# band-psd-micro-standalone.net
KiCad netlist of a schematic drawn in EAGLE
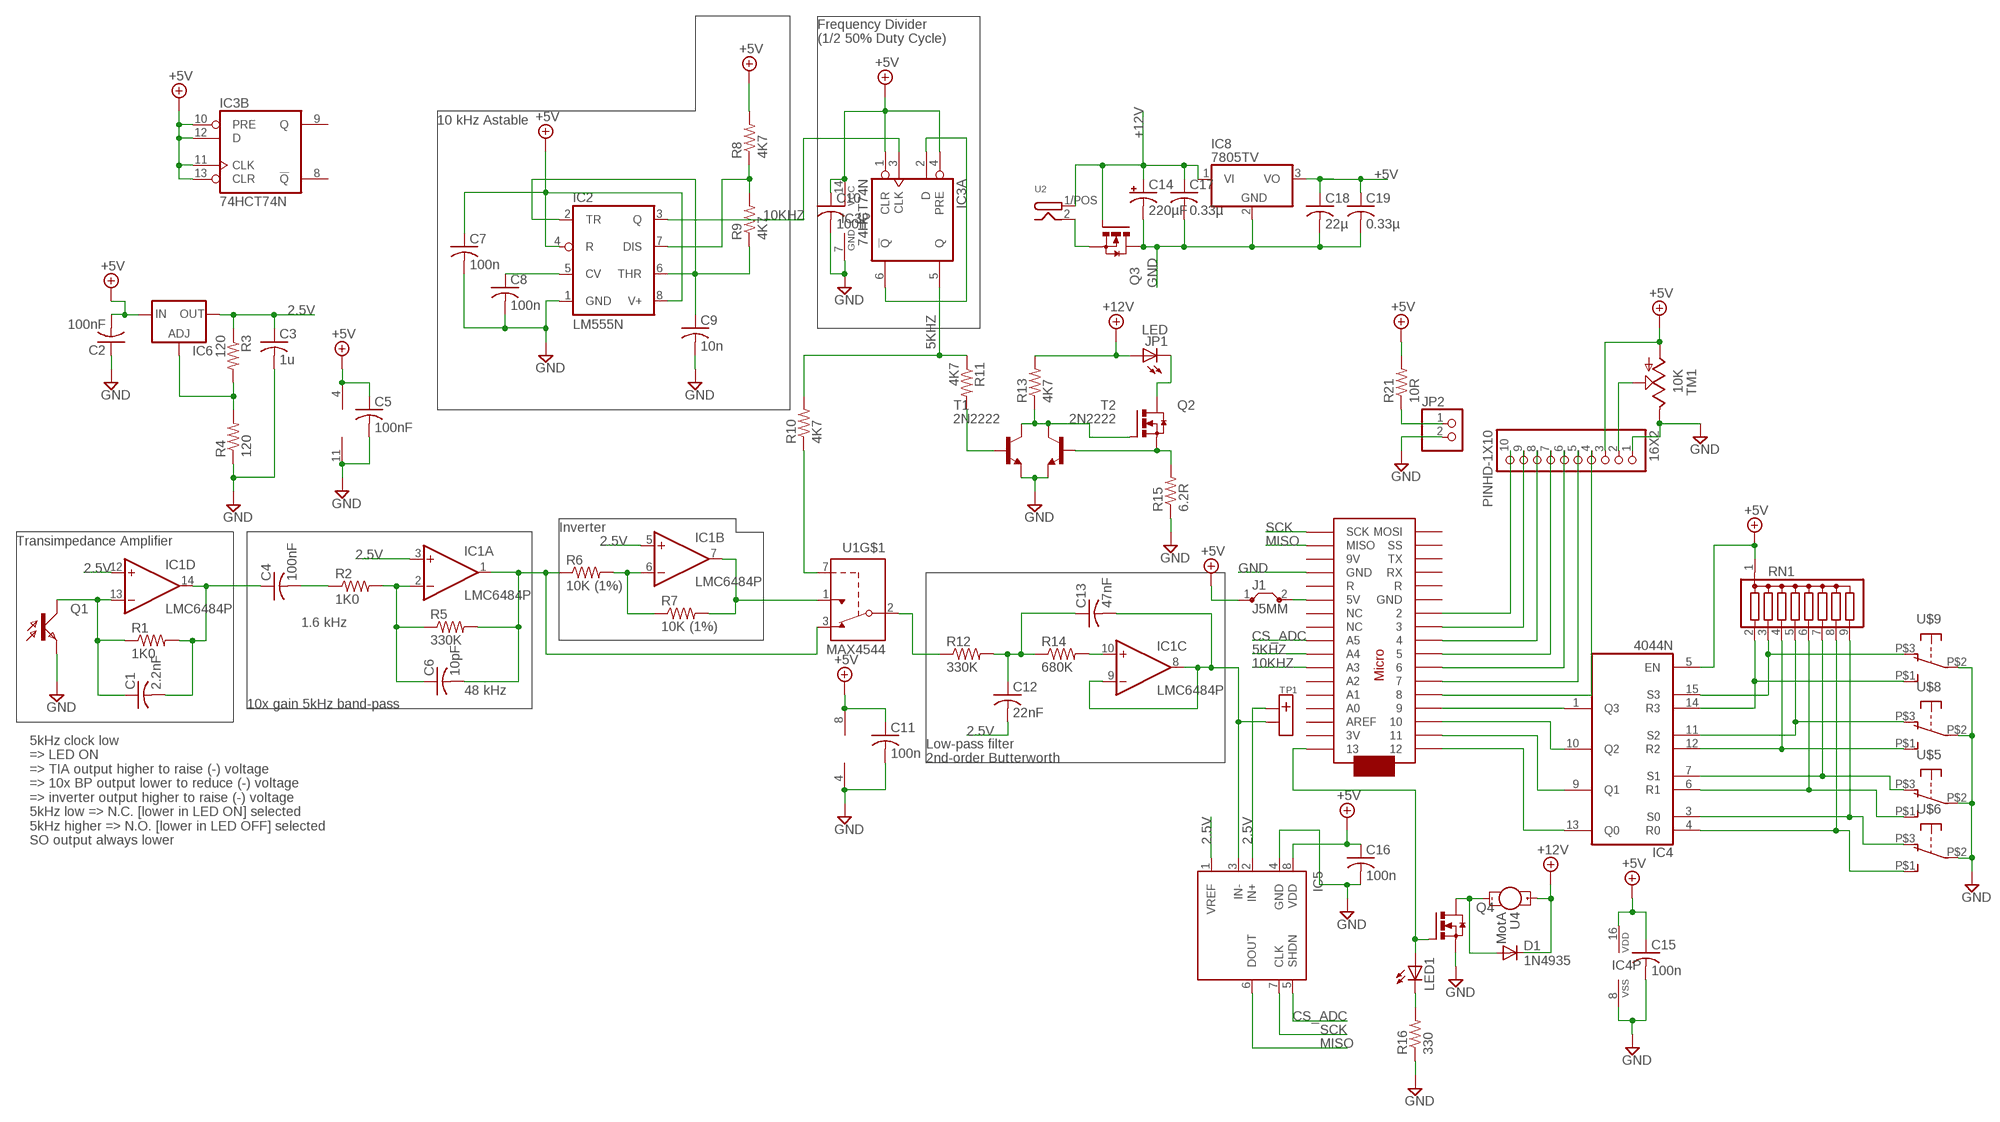
[diagram p0: schematic, sheet 1]

(export (version "E")
  (design (tool "Eeschema 10.0.6"))
  (components
    (comp (ref "16X2")
      (value "PINHD-1X10")
      (footprint "eagle-import:1X10-BIG")
      (libsource (lib "eagle-import") (part "PINHD-1X10"))
    )
    (comp (ref "C1")
      (value "2.2nF")
      (footprint "eagle-import:C025-024X044")
      (fields (field (name "MANF") "Vishay BC Components"))
      (libsource (lib "eagle-import") (part "C-US025-024X044"))
    )
    (comp (ref "C2")
      (value "100nF")
      (footprint "eagle-import:C025-025X050")
      (fields (field (name "MANF") "Vishay BC Components"))
      (libsource (lib "eagle-import") (part "C-US025-025X050"))
    )
    (comp (ref "C3")
      (value "1u")
      (footprint "eagle-import:C050-024X044")
      (fields (field (name "MANF") "TDK Corporation"))
      (libsource (lib "eagle-import") (part "C-US050-024X044"))
    )
    (comp (ref "C4")
      (value "100nF")
      (footprint "eagle-import:C025-060X050")
      (fields (field (name "MANF") "TDK Corporation"))
      (libsource (lib "eagle-import") (part "C-US025-060X050"))
    )
    (comp (ref "C5")
      (value "100nF")
      (footprint "eagle-import:C025-025X050")
      (libsource (lib "eagle-import") (part "C-US025-025X050"))
    )
    (comp (ref "C6")
      (value "10pF")
      (footprint "eagle-import:C025-024X044")
      (fields (field (name "MANF") "Vishay BC Components"))
      (libsource (lib "eagle-import") (part "C-US025-024X044"))
    )
    (comp (ref "C7")
      (value "100n")
      (footprint "eagle-import:C025-025X050")
      (libsource (lib "eagle-import") (part "C-US025-025X050"))
    )
    (comp (ref "C8")
      (value "100n")
      (footprint "eagle-import:C025-025X050")
      (libsource (lib "eagle-import") (part "C-US025-025X050"))
    )
    (comp (ref "C9")
      (value "10n")
      (footprint "eagle-import:C025-025X050")
      (fields (field (name "MANF") "TDK Corporation"))
      (libsource (lib "eagle-import") (part "C-US025-025X050"))
    )
    (comp (ref "C10")
      (value "100n")
      (footprint "eagle-import:C025-025X050")
      (libsource (lib "eagle-import") (part "C-US025-025X050"))
    )
    (comp (ref "C11")
      (value "100n")
      (footprint "eagle-import:C025-025X050")
      (libsource (lib "eagle-import") (part "C-US025-025X050"))
    )
    (comp (ref "C12")
      (value "22nF")
      (footprint "eagle-import:C025-024X044")
      (fields (field (name "MANF") "TDK Corporation"))
      (libsource (lib "eagle-import") (part "C-US025-024X044"))
    )
    (comp (ref "C13")
      (value "47nF")
      (footprint "eagle-import:C025-040X050")
      (fields (field (name "MANF") "TDK Corporation"))
      (libsource (lib "eagle-import") (part "C-US025-040X050"))
    )
    (comp (ref "C14")
      (value "220µF")
      (footprint "eagle-import:E3,5-8")
      (fields (field (name "MANF") "Panasonic Electronic Components"))
      (libsource (lib "eagle-import") (part "CPOL-USE3.5-8"))
    )
    (comp (ref "C15")
      (value "100n")
      (footprint "eagle-import:C025-025X050")
      (libsource (lib "eagle-import") (part "C-US025-025X050"))
    )
    (comp (ref "C16")
      (value "100n")
      (footprint "eagle-import:C025-025X050")
      (libsource (lib "eagle-import") (part "C-US025-025X050"))
    )
    (comp (ref "C17")
      (value "0.33µ")
      (footprint "eagle-import:C025-050X050")
      (fields (field (name "MANF") "TDK Corporation"))
      (libsource (lib "eagle-import") (part "C-US025-050X050"))
    )
    (comp (ref "C18")
      (value "22µ")
      (footprint "eagle-import:C050-045X075")
      (fields (field (name "MANF") "TDK Corporation"))
      (libsource (lib "eagle-import") (part "C-US050-045X075"))
    )
    (comp (ref "C19")
      (value "0.33µ")
      (footprint "eagle-import:C025-050X050")
      (fields (field (name "MANF") "TDK Corporation"))
      (libsource (lib "eagle-import") (part "C-US025-050X050"))
    )
    (comp (ref "D1")
      (value "1N4935")
      (footprint "eagle-import:DO41-10")
      (fields (field (name "MANF") "Fairchild Semiconductor"))
      (libsource (lib "eagle-import") (part "1N4004"))
    )
    (comp (ref "IC1")
      (value "LMC6484P")
      (footprint "eagle-import:DIL14")
      (fields
        (field (name "DIGIKEY#") "LMC6484AIN/NOPB-ND")
        (field (name "DIGIKEY2#") "AE10012-ND")
        (field (name "MANF") "Texas Instruments")
        (field (name "MANF#") "LMC6484AIN/NOPB")
      )
      (libsource (lib "eagle-import") (part "LMC6484P"))
    )
    (comp (ref "IC2")
      (value "LM555N")
      (footprint "eagle-import:DIL08")
      (fields (field (name "MANF") "Fairchild Semiconductor"))
      (libsource (lib "eagle-import") (part "555NLM"))
    )
    (comp (ref "IC3")
      (value "74HCT74N")
      (footprint "eagle-import:DIL14")
      (fields
        (field (name "DIGIKEY#") "296-1625-5-ND ")
        (field (name "DIGIKEY2#") "AE10012-ND")
        (field (name "MANF") "Texas Instruments")
        (field (name "MANF#") "SN74HCT74N")
      )
      (libsource (lib "eagle-import") (part "7474NHCT"))
    )
    (comp (ref "IC4")
      (value "4044N")
      (footprint "eagle-import:DIL16")
      (fields
        (field (name "MANF") "Texas Instruments")
        (field (name "DIGIKEY#") "296-2051-5-ND ")
        (field (name "DIGIKEY2#") "AE9992-ND")
        (field (name "MANF#") "CD4044BE")
      )
      (libsource (lib "eagle-import") (part "4044N"))
    )
    (comp (ref "IC5")
      (value "MCP3301")
      (footprint "eagle-import:DIL08")
      (fields (field (name "MANF") "Microchip Technology"))
      (libsource (lib "eagle-import") (part "MCP3301"))
    )
    (comp (ref "IC6")
      (value "LM317L")
      (footprint "eagle-import:317L")
      (fields (field (name "MANF") "Texas Instruments"))
      (libsource (lib "eagle-import") (part "LM317L"))
    )
    (comp (ref "IC8")
      (value "7805TV")
      (footprint "eagle-import:TO220V")
      (fields (field (name "MANF") "Fairchild Semiconductor"))
      (libsource (lib "eagle-import") (part "78TV05"))
    )
    (comp (ref "J1")
      (value "J5MM")
      (footprint "eagle-import:05")
      (fields (field (name "MANF") "Yageo"))
      (libsource (lib "eagle-import") (part "J5MM"))
    )
    (comp (ref "JP1")
      (value "LED")
      (footprint "eagle-import:1X02_SCREW")
      (fields (field (name "MANF") "OSRAM Opto Semiconductors Inc"))
      (libsource (lib "eagle-import") (part "LED_CXN"))
    )
    (comp (ref "JP2")
      (value "PINHD-1X2")
      (footprint "eagle-import:1X02")
      (libsource (lib "eagle-import") (part "PINHD-1X2"))
    )
    (comp (ref "LED1")
      (value "LED3MM")
      (footprint "eagle-import:LED3MM")
      (fields (field (name "MANF") "Lite-On Inc"))
      (libsource (lib "eagle-import") (part "LED3MM"))
    )
    (comp (ref "Q1")
      (value "LTR-4206")
      (footprint "eagle-import:3MM_LED")
      (fields (field (name "MANF") "Lite-On Inc"))
      (libsource (lib "eagle-import") (part "LTR-4206"))
    )
    (comp (ref "Q2")
      (value "IRLB8721")
      (footprint "eagle-import:TO220BV")
      (libsource (lib "eagle-import") (part "IRLB8721"))
    )
    (comp (ref "Q3")
      (value "IRLB8721")
      (footprint "eagle-import:TO220BV")
      (fields (field (name "MANF") "International Rectifier"))
      (libsource (lib "eagle-import") (part "IRLB8721"))
    )
    (comp (ref "Q4")
      (value "IRLB8721")
      (footprint "eagle-import:TO220BV")
      (fields (field (name "MANF") "International Rectifier"))
      (libsource (lib "eagle-import") (part "IRLB8721"))
    )
    (comp (ref "R1")
      (value "1K0")
      (footprint "eagle-import:0204_5")
      (fields (field (name "MANF") "Stackpole Electronics Inc"))
      (libsource (lib "eagle-import") (part "R-US_0204/5"))
    )
    (comp (ref "R2")
      (value "1K0")
      (footprint "eagle-import:0204_5")
      (fields (field (name "MANF") "Stackpole Electronics Inc"))
      (libsource (lib "eagle-import") (part "R-US_0204/5"))
    )
    (comp (ref "R3")
      (value "120")
      (footprint "eagle-import:0204V")
      (fields (field (name "MANF") "Stackpole Electronics Inc"))
      (libsource (lib "eagle-import") (part "R-US_0204/2V"))
    )
    (comp (ref "R4")
      (value "120")
      (footprint "eagle-import:0204V")
      (fields (field (name "MANF") "Stackpole Electronics Inc"))
      (libsource (lib "eagle-import") (part "R-US_0204/2V"))
    )
    (comp (ref "R5")
      (value "330K")
      (footprint "eagle-import:0309V")
      (fields (field (name "MANF") "Stackpole Electronics Inc"))
      (libsource (lib "eagle-import") (part "R-US_0309/V"))
    )
    (comp (ref "R6")
      (value "10K (1%)")
      (footprint "eagle-import:0204_5")
      (fields (field (name "MANF") "Stackpole Electronics Inc"))
      (libsource (lib "eagle-import") (part "R-US_0204/5"))
    )
    (comp (ref "R7")
      (value "10K (1%)")
      (footprint "eagle-import:0204_5")
      (fields (field (name "MANF") "Stackpole Electronics Inc"))
      (libsource (lib "eagle-import") (part "R-US_0204/5"))
    )
    (comp (ref "R8")
      (value "4K7")
      (footprint "eagle-import:0204V")
      (fields (field (name "MANF") "Stackpole Electronics Inc"))
      (libsource (lib "eagle-import") (part "R-US_0204/2V"))
    )
    (comp (ref "R9")
      (value "4K7")
      (footprint "eagle-import:0204V")
      (fields (field (name "MANF") "Stackpole Electronics Inc"))
      (libsource (lib "eagle-import") (part "R-US_0204/2V"))
    )
    (comp (ref "R10")
      (value "4K7")
      (footprint "eagle-import:0204V")
      (fields (field (name "MANF") "Stackpole Electronics Inc"))
      (libsource (lib "eagle-import") (part "R-US_0204/2V"))
    )
    (comp (ref "R11")
      (value "4K7")
      (footprint "eagle-import:0204V")
      (fields (field (name "MANF") "Stackpole Electronics Inc"))
      (libsource (lib "eagle-import") (part "R-US_0204/2V"))
    )
    (comp (ref "R12")
      (value "330K")
      (footprint "eagle-import:0204V")
      (fields (field (name "MANF") "Stackpole Electronics Inc"))
      (libsource (lib "eagle-import") (part "R-US_0204/2V"))
    )
    (comp (ref "R13")
      (value "4K7")
      (footprint "eagle-import:0204V")
      (fields (field (name "MANF") "Stackpole Electronics Inc"))
      (libsource (lib "eagle-import") (part "R-US_0204/2V"))
    )
    (comp (ref "R14")
      (value "680K")
      (footprint "eagle-import:0204V")
      (fields (field (name "MANF") "Stackpole Electronics Inc"))
      (libsource (lib "eagle-import") (part "R-US_0204/2V"))
    )
    (comp (ref "R15")
      (value "6.2R")
      (footprint "eagle-import:0204V")
      (fields (field (name "MANF") "Vishay BC Components"))
      (libsource (lib "eagle-import") (part "R-US_0204/2V"))
    )
    (comp (ref "R16")
      (value "330")
      (footprint "eagle-import:0204V")
      (fields (field (name "MANF") "Stackpole Electronics Inc"))
      (libsource (lib "eagle-import") (part "R-US_0204/2V"))
    )
    (comp (ref "R21")
      (value "10R")
      (footprint "eagle-import:0204V")
      (libsource (lib "eagle-import") (part "R-US_0204/2V"))
    )
    (comp (ref "RN1")
      (value "G08R")
      (footprint "eagle-import:SIL9")
      (fields (field (name "MANF") "Bourns Inc."))
      (libsource (lib "eagle-import") (part "G08R"))
    )
    (comp (ref "T1")
      (value "2N2222")
      (footprint "eagle-import:TO92-EBC-OVAL")
      (fields (field (name "MANF") "Fairchild Semiconductor"))
      (libsource (lib "eagle-import") (part "2N2222"))
    )
    (comp (ref "T2")
      (value "2N2222")
      (footprint "eagle-import:TO92-EBC-OVAL")
      (fields (field (name "MANF") "Fairchild Semiconductor"))
      (libsource (lib "eagle-import") (part "2N2222"))
    )
    (comp (ref "TM1")
      (value "10K")
      (footprint "eagle-import:B25P")
      (fields (field (name "MANF") "Bourns Inc."))
      (libsource (lib "eagle-import") (part "TRIM_US-B25P"))
    )
    (comp (ref "TP1")
      (value "TEST_POINT")
      (footprint "eagle-import:1X02_SCREW")
      (libsource (lib "eagle-import") (part "TEST_POINT"))
    )
    (comp (ref "U$5")
      (value "APE1F-5M-10-Z")
      (footprint "eagle-import:APE1F-5M-10Z")
      (libsource (lib "eagle-import") (part "APE1F-5M-10-Z"))
    )
    (comp (ref "U$6")
      (value "APE1F-5M-10-Z")
      (footprint "eagle-import:APE1F-5M-10Z")
      (libsource (lib "eagle-import") (part "APE1F-5M-10-Z"))
    )
    (comp (ref "U$8")
      (value "APE1F-5M-10-Z")
      (footprint "eagle-import:APE1F-5M-10Z")
      (libsource (lib "eagle-import") (part "APE1F-5M-10-Z"))
    )
    (comp (ref "U$9")
      (value "APE1F-5M-10-Z")
      (footprint "eagle-import:APE1F-5M-10Z")
      (fields (field (name "MANF") "Copal Electronics Inc"))
      (libsource (lib "eagle-import") (part "APE1F-5M-10-Z"))
    )
    (comp (ref "U1")
      (value "MAX4544")
      (footprint "eagle-import:DIL08")
      (fields
        (field (name "DIGIKEY#") "MAX4544CPA+-ND")
        (field (name "DIGIKEY2#") "AE9986-ND")
        (field (name "MANF") "Maxim Integrated")
        (field (name "MANF#") "MAX4544CPA+")
      )
      (libsource (lib "eagle-import") (part "MAX4544"))
    )
    (comp (ref "U2")
      (value "DC-IN-PANEL-NODETECT")
      (footprint "eagle-import:1X02_SCREW")
      (fields (field (name "MANF") "CUI Inc"))
      (libsource (lib "eagle-import") (part "DC-IN-PANEL-NODETECT"))
    )
    (comp (ref "U3")
      (value "ARDUINOMICRO")
      (footprint "eagle-import:ARDUINOMICRO")
      (fields (field (name "MANF") "Arduino"))
      (libsource (lib "eagle-import") (part "ARDUINOMICRO"))
    )
    (comp (ref "U4")
      (value "MotA")
      (footprint "eagle-import:1X02_SCREW")
      (fields (field (name "MANF") "Switchcraft Inc."))
      (libsource (lib "eagle-import") (part "1X02_MOTOR"))
    )
  )
  (nets
    (net (code "1") (name "+5V") (class "Default")
      (node (ref "16X2") (pin "3") (pinfunction "3_3") (pintype "passive"))
      (node (ref "C10") (pin "1") (pinfunction "1_1") (pintype "passive"))
      (node (ref "C11") (pin "1") (pinfunction "1_1") (pintype "passive"))
      (node (ref "C15") (pin "1") (pinfunction "1_1") (pintype "passive"))
      (node (ref "C16") (pin "1") (pinfunction "1_1") (pintype "passive"))
      (node (ref "C18") (pin "1") (pinfunction "1_1") (pintype "passive"))
      (node (ref "C19") (pin "1") (pinfunction "1_1") (pintype "passive"))
      (node (ref "C2") (pin "2") (pinfunction "2_2") (pintype "passive"))
      (node (ref "C5") (pin "1") (pinfunction "1_1") (pintype "passive"))
      (node (ref "C7") (pin "1") (pinfunction "1_1") (pintype "passive"))
      (node (ref "IC1") (pin "4") (pinfunction "V+_4") (pintype "power_in"))
      (node (ref "IC2") (pin "4") (pinfunction "R_4") (pintype "input"))
      (node (ref "IC2") (pin "8") (pinfunction "V+_8") (pintype "power_in"))
      (node (ref "IC3") (pin "1") (pinfunction "CLR_1") (pintype "input"))
      (node (ref "IC3") (pin "10") (pinfunction "PRE_10") (pintype "input"))
      (node (ref "IC3") (pin "11") (pinfunction "CLK_11") (pintype "input"))
      (node (ref "IC3") (pin "12") (pinfunction "D_12") (pintype "input"))
      (node (ref "IC3") (pin "13") (pinfunction "CLR_13") (pintype "input"))
      (node (ref "IC3") (pin "14") (pinfunction "VCC_14") (pintype "power_in"))
      (node (ref "IC3") (pin "4") (pinfunction "PRE_4") (pintype "input"))
      (node (ref "IC4") (pin "16") (pinfunction "VDD_16") (pintype "power_in"))
      (node (ref "IC4") (pin "5") (pinfunction "EN_5") (pintype "input"))
      (node (ref "IC5") (pin "8") (pinfunction "VDD_8") (pintype "power_in"))
      (node (ref "IC6") (pin "3") (pinfunction "IN_3") (pintype "input"))
      (node (ref "IC8") (pin "3") (pinfunction "VO_3") (pintype "passive"))
      (node (ref "J1") (pin "1") (pinfunction "1_1") (pintype "passive"))
      (node (ref "R21") (pin "2") (pinfunction "2_2") (pintype "passive"))
      (node (ref "R8") (pin "2") (pinfunction "2_2") (pintype "passive"))
      (node (ref "RN1") (pin "1") (pinfunction "1_1") (pintype "passive"))
      (node (ref "TM1") (pin "A") (pinfunction "A_A") (pintype "passive"))
      (node (ref "U1") (pin "8") (pinfunction "V+_8") (pintype "power_in"))
    )
    (net (code "2") (name "+12V") (class "Default")
      (node (ref "C14") (pin "+") (pinfunction "+_+") (pintype "passive"))
      (node (ref "C17") (pin "1") (pinfunction "1_1") (pintype "passive"))
      (node (ref "D1") (pin "C") (pinfunction "C_C") (pintype "passive"))
      (node (ref "IC8") (pin "1") (pinfunction "VI_1") (pintype "input"))
      (node (ref "JP1") (pin "1/POS") (pinfunction "A_1/POS") (pintype "passive"))
      (node (ref "Q3") (pin "G") (pinfunction "G_G") (pintype "passive"))
      (node (ref "R13") (pin "2") (pinfunction "2_2") (pintype "passive"))
      (node (ref "U2") (pin "1/POS") (pinfunction "PWR_1/POS") (pintype "power_in"))
      (node (ref "U4") (pin "1/POS") (pinfunction "+_1/POS") (pintype "bidirectional"))
    )
    (net (code "3") (name "/2.5V") (class "Default")
      (node (ref "C12") (pin "2") (pinfunction "2_2") (pintype "passive"))
      (node (ref "C3") (pin "1") (pinfunction "1_1") (pintype "passive"))
      (node (ref "IC1") (pin "12") (pinfunction "+IN_12") (pintype "input"))
      (node (ref "IC1") (pin "3") (pinfunction "+IN_3") (pintype "input"))
      (node (ref "IC1") (pin "5") (pinfunction "+IN_5") (pintype "input"))
      (node (ref "IC5") (pin "1") (pinfunction "VREF_1") (pintype "input"))
      (node (ref "IC5") (pin "2") (pinfunction "IN+_2") (pintype "input"))
      (node (ref "IC6") (pin "2") (pinfunction "OUT_2") (pintype "passive"))
      (node (ref "R3") (pin "1") (pinfunction "1_1") (pintype "passive"))
      (node (ref "TP1") (pin "1/POS") (pinfunction "+_1/POS") (pintype "passive"))
    )
    (net (code "4") (name "/5KHZ") (class "Default")
      (node (ref "IC3") (pin "5") (pinfunction "Q_5") (pintype "output"))
      (node (ref "R10") (pin "2") (pinfunction "2_2") (pintype "passive"))
      (node (ref "R11") (pin "1") (pinfunction "1_1") (pintype "passive"))
      (node (ref "U3") (pin "P$27") (pinfunction "A4_P$27") (pintype "bidirectional"))
    )
    (net (code "5") (name "/10KHZ") (class "Default")
      (node (ref "IC2") (pin "3") (pinfunction "Q_3") (pintype "output"))
      (node (ref "IC3") (pin "3") (pinfunction "CLK_3") (pintype "input"))
      (node (ref "U3") (pin "P$28") (pinfunction "A3_P$28") (pintype "bidirectional"))
    )
    (net (code "6") (name "/CS_ADC") (class "Default")
      (node (ref "IC5") (pin "5") (pinfunction "SHDN_5") (pintype "input"))
      (node (ref "U3") (pin "P$26") (pinfunction "A5_P$26") (pintype "bidirectional"))
    )
    (net (code "7") (name "/MISO") (class "Default")
      (node (ref "IC5") (pin "6") (pinfunction "DOUT_6") (pintype "input"))
      (node (ref "U3") (pin "P$19") (pinfunction "MISO_P$19") (pintype "bidirectional"))
    )
    (net (code "8") (name "/SCK") (class "Default")
      (node (ref "IC5") (pin "7") (pinfunction "CLK_7") (pintype "input"))
      (node (ref "U3") (pin "P$18") (pinfunction "SCK_P$18") (pintype "bidirectional"))
    )
    (net (code "9") (name "GND") (class "Default")
      (node (ref "16X2") (pin "1") (pinfunction "1_1") (pintype "passive"))
      (node (ref "C10") (pin "2") (pinfunction "2_2") (pintype "passive"))
      (node (ref "C11") (pin "2") (pinfunction "2_2") (pintype "passive"))
      (node (ref "C14") (pin "-") (pinfunction "-_-") (pintype "passive"))
      (node (ref "C15") (pin "2") (pinfunction "2_2") (pintype "passive"))
      (node (ref "C16") (pin "2") (pinfunction "2_2") (pintype "passive"))
      (node (ref "C17") (pin "2") (pinfunction "2_2") (pintype "passive"))
      (node (ref "C18") (pin "2") (pinfunction "2_2") (pintype "passive"))
      (node (ref "C19") (pin "2") (pinfunction "2_2") (pintype "passive"))
      (node (ref "C2") (pin "1") (pinfunction "1_1") (pintype "passive"))
      (node (ref "C3") (pin "2") (pinfunction "2_2") (pintype "passive"))
      (node (ref "C5") (pin "2") (pinfunction "2_2") (pintype "passive"))
      (node (ref "C7") (pin "2") (pinfunction "2_2") (pintype "passive"))
      (node (ref "C8") (pin "2") (pinfunction "2_2") (pintype "passive"))
      (node (ref "C9") (pin "2") (pinfunction "2_2") (pintype "passive"))
      (node (ref "IC1") (pin "11") (pinfunction "V-_11") (pintype "power_in"))
      (node (ref "IC2") (pin "1") (pinfunction "GND_1") (pintype "power_in"))
      (node (ref "IC3") (pin "7") (pinfunction "GND_7") (pintype "power_in"))
      (node (ref "IC4") (pin "8") (pinfunction "VSS_8") (pintype "power_in"))
      (node (ref "IC5") (pin "4") (pinfunction "GND_4") (pintype "power_in"))
      (node (ref "IC8") (pin "2") (pinfunction "GND_2") (pintype "passive"))
      (node (ref "JP2") (pin "2") (pinfunction "2_2") (pintype "passive"))
      (node (ref "Q1") (pin "A") (pinfunction "E_A") (pintype "passive"))
      (node (ref "Q3") (pin "D") (pinfunction "D_D") (pintype "passive"))
      (node (ref "Q4") (pin "S") (pinfunction "S_S") (pintype "passive"))
      (node (ref "R15") (pin "1") (pinfunction "1_1") (pintype "passive"))
      (node (ref "R16") (pin "1") (pinfunction "1_1") (pintype "passive"))
      (node (ref "R4") (pin "1") (pinfunction "1_1") (pintype "passive"))
      (node (ref "T1") (pin "E") (pinfunction "E_E") (pintype "passive"))
      (node (ref "T2") (pin "E") (pinfunction "E_E") (pintype "passive"))
      (node (ref "TM1") (pin "E") (pinfunction "E_E") (pintype "passive"))
      (node (ref "U$5") (pin "P$2") (pinfunction "COM_P$2") (pintype "passive"))
      (node (ref "U$6") (pin "P$2") (pinfunction "COM_P$2") (pintype "passive"))
      (node (ref "U$8") (pin "P$2") (pinfunction "COM_P$2") (pintype "passive"))
      (node (ref "U$9") (pin "P$2") (pinfunction "COM_P$2") (pintype "passive"))
      (node (ref "U1") (pin "4") (pinfunction "V-_4") (pintype "power_in"))
      (node (ref "U3") (pin "P$12") (pinfunction "GND_P$12") (pintype "bidirectional"))
    )
    (net (code "10") (name "Net-(16X2-Pad2)") (class "Default")
      (node (ref "16X2") (pin "2") (pinfunction "2_2") (pintype "passive"))
      (node (ref "TM1") (pin "S") (pinfunction "S_S") (pintype "passive"))
    )
    (net (code "11") (name "Net-(C4-Pad2)") (class "Default")
      (node (ref "C4") (pin "2") (pinfunction "2_2") (pintype "passive"))
      (node (ref "R2") (pin "1") (pinfunction "1_1") (pintype "passive"))
    )
    (net (code "12") (name "Net-(C12-Pad1)") (class "Default")
      (node (ref "C12") (pin "1") (pinfunction "1_1") (pintype "passive"))
      (node (ref "C13") (pin "1") (pinfunction "1_1") (pintype "passive"))
      (node (ref "R12") (pin "2") (pinfunction "2_2") (pintype "passive"))
      (node (ref "R14") (pin "1") (pinfunction "1_1") (pintype "passive"))
    )
    (net (code "13") (name "Net-(IC1A--IN)") (class "Default")
      (node (ref "C6") (pin "1") (pinfunction "1_1") (pintype "passive"))
      (node (ref "IC1") (pin "2") (pinfunction "-IN_2") (pintype "input"))
      (node (ref "R2") (pin "2") (pinfunction "2_2") (pintype "passive"))
      (node (ref "R5") (pin "1") (pinfunction "1_1") (pintype "passive"))
    )
    (net (code "14") (name "Net-(IC1A-OUT)") (class "Default")
      (node (ref "C6") (pin "2") (pinfunction "2_2") (pintype "passive"))
      (node (ref "IC1") (pin "1") (pinfunction "OUT_1") (pintype "output"))
      (node (ref "R5") (pin "2") (pinfunction "2_2") (pintype "passive"))
      (node (ref "R6") (pin "1") (pinfunction "1_1") (pintype "passive"))
      (node (ref "U1") (pin "3") (pinfunction "NC_3") (pintype "bidirectional"))
    )
    (net (code "15") (name "Net-(IC1B--IN)") (class "Default")
      (node (ref "IC1") (pin "6") (pinfunction "-IN_6") (pintype "input"))
      (node (ref "R6") (pin "2") (pinfunction "2_2") (pintype "passive"))
      (node (ref "R7") (pin "1") (pinfunction "1_1") (pintype "passive"))
    )
    (net (code "16") (name "Net-(IC1B-OUT)") (class "Default")
      (node (ref "IC1") (pin "7") (pinfunction "OUT_7") (pintype "output"))
      (node (ref "R7") (pin "2") (pinfunction "2_2") (pintype "passive"))
      (node (ref "U1") (pin "1") (pinfunction "NO_1") (pintype "bidirectional"))
    )
    (net (code "17") (name "Net-(IC1C-+IN)") (class "Default")
      (node (ref "IC1") (pin "10") (pinfunction "+IN_10") (pintype "input"))
      (node (ref "R14") (pin "2") (pinfunction "2_2") (pintype "passive"))
    )
    (net (code "18") (name "Net-(IC1C--IN)") (class "Default")
      (node (ref "C13") (pin "2") (pinfunction "2_2") (pintype "passive"))
      (node (ref "IC1") (pin "8") (pinfunction "OUT_8") (pintype "output"))
      (node (ref "IC1") (pin "9") (pinfunction "-IN_9") (pintype "input"))
      (node (ref "IC5") (pin "3") (pinfunction "IN-_3") (pintype "input"))
      (node (ref "TP1") (pin "2") (pinfunction "-_2") (pintype "passive"))
    )
    (net (code "19") (name "Net-(IC1D--IN)") (class "Default")
      (node (ref "C1") (pin "1") (pinfunction "1_1") (pintype "passive"))
      (node (ref "IC1") (pin "13") (pinfunction "-IN_13") (pintype "input"))
      (node (ref "Q1") (pin "K") (pinfunction "C_K") (pintype "passive"))
      (node (ref "R1") (pin "1") (pinfunction "1_1") (pintype "passive"))
    )
    (net (code "20") (name "Net-(IC1D-OUT)") (class "Default")
      (node (ref "C1") (pin "2") (pinfunction "2_2") (pintype "passive"))
      (node (ref "C4") (pin "1") (pinfunction "1_1") (pintype "passive"))
      (node (ref "IC1") (pin "14") (pinfunction "OUT_14") (pintype "output"))
      (node (ref "R1") (pin "2") (pinfunction "2_2") (pintype "passive"))
    )
    (net (code "21") (name "Net-(IC2-CV)") (class "Default")
      (node (ref "C8") (pin "1") (pinfunction "1_1") (pintype "passive"))
      (node (ref "IC2") (pin "5") (pinfunction "CV_5") (pintype "input"))
    )
    (net (code "22") (name "Net-(IC2-DIS)") (class "Default")
      (node (ref "IC2") (pin "7") (pinfunction "DIS_7") (pintype "input"))
      (node (ref "R8") (pin "1") (pinfunction "1_1") (pintype "passive"))
      (node (ref "R9") (pin "2") (pinfunction "2_2") (pintype "passive"))
    )
    (net (code "23") (name "Net-(IC2-THR)") (class "Default")
      (node (ref "C9") (pin "1") (pinfunction "1_1") (pintype "passive"))
      (node (ref "IC2") (pin "2") (pinfunction "TR_2") (pintype "input"))
      (node (ref "IC2") (pin "6") (pinfunction "THR_6") (pintype "input"))
      (node (ref "R9") (pin "1") (pinfunction "1_1") (pintype "passive"))
    )
    (net (code "24") (name "Net-(IC3A-D)") (class "Default")
      (node (ref "IC3") (pin "2") (pinfunction "D_2") (pintype "input"))
      (node (ref "IC3") (pin "6") (pinfunction "~{Q}_6") (pintype "output"))
    )
    (net (code "25") (name "Net-(IC4A-Q0)") (class "Default")
      (node (ref "IC4") (pin "13") (pinfunction "Q0_13") (pintype "output"))
      (node (ref "U3") (pin "P$1") (pinfunction "12_P$1") (pintype "bidirectional"))
    )
    (net (code "26") (name "Net-(IC4A-Q1)") (class "Default")
      (node (ref "IC4") (pin "9") (pinfunction "Q1_9") (pintype "output"))
      (node (ref "U3") (pin "P$2") (pinfunction "11_P$2") (pintype "bidirectional"))
    )
    (net (code "27") (name "Net-(IC4A-Q2)") (class "Default")
      (node (ref "IC4") (pin "10") (pinfunction "Q2_10") (pintype "output"))
      (node (ref "U3") (pin "P$3") (pinfunction "10_P$3") (pintype "bidirectional"))
    )
    (net (code "28") (name "Net-(IC4A-Q3)") (class "Default")
      (node (ref "IC4") (pin "1") (pinfunction "Q3_1") (pintype "output"))
      (node (ref "U3") (pin "P$4") (pinfunction "9_P$4") (pintype "bidirectional"))
    )
    (net (code "29") (name "Net-(IC4A-R0)") (class "Default")
      (node (ref "IC4") (pin "4") (pinfunction "R0_4") (pintype "input"))
      (node (ref "RN1") (pin "8") (pinfunction "8_8") (pintype "passive"))
      (node (ref "U$6") (pin "P$1") (pinfunction "NO_P$1") (pintype "passive"))
    )
    (net (code "30") (name "Net-(IC4A-R1)") (class "Default")
      (node (ref "IC4") (pin "6") (pinfunction "R1_6") (pintype "input"))
      (node (ref "RN1") (pin "6") (pinfunction "6_6") (pintype "passive"))
      (node (ref "U$5") (pin "P$1") (pinfunction "NO_P$1") (pintype "passive"))
    )
    (net (code "31") (name "Net-(IC4A-R2)") (class "Default")
      (node (ref "IC4") (pin "12") (pinfunction "R2_12") (pintype "input"))
      (node (ref "RN1") (pin "4") (pinfunction "4_4") (pintype "passive"))
      (node (ref "U$8") (pin "P$1") (pinfunction "NO_P$1") (pintype "passive"))
    )
    (net (code "32") (name "Net-(IC4A-R3)") (class "Default")
      (node (ref "IC4") (pin "14") (pinfunction "R3_14") (pintype "input"))
      (node (ref "RN1") (pin "2") (pinfunction "2_2") (pintype "passive"))
      (node (ref "U$9") (pin "P$1") (pinfunction "NO_P$1") (pintype "passive"))
    )
    (net (code "33") (name "Net-(IC4A-S0)") (class "Default")
      (node (ref "IC4") (pin "3") (pinfunction "S0_3") (pintype "input"))
      (node (ref "RN1") (pin "9") (pinfunction "9_9") (pintype "passive"))
      (node (ref "U$6") (pin "P$3") (pinfunction "NC_P$3") (pintype "passive"))
    )
    (net (code "34") (name "Net-(IC4A-S1)") (class "Default")
      (node (ref "IC4") (pin "7") (pinfunction "S1_7") (pintype "input"))
      (node (ref "RN1") (pin "7") (pinfunction "7_7") (pintype "passive"))
      (node (ref "U$5") (pin "P$3") (pinfunction "NC_P$3") (pintype "passive"))
    )
    (net (code "35") (name "Net-(IC4A-S2)") (class "Default")
      (node (ref "IC4") (pin "11") (pinfunction "S2_11") (pintype "input"))
      (node (ref "RN1") (pin "5") (pinfunction "5_5") (pintype "passive"))
      (node (ref "U$8") (pin "P$3") (pinfunction "NC_P$3") (pintype "passive"))
    )
    (net (code "36") (name "Net-(IC4A-S3)") (class "Default")
      (node (ref "IC4") (pin "15") (pinfunction "S3_15") (pintype "input"))
      (node (ref "RN1") (pin "3") (pinfunction "3_3") (pintype "passive"))
      (node (ref "U$9") (pin "P$3") (pinfunction "NC_P$3") (pintype "passive"))
    )
    (net (code "37") (name "Net-(IC6-ADJ)") (class "Default")
      (node (ref "IC6") (pin "1") (pinfunction "ADJ_1") (pintype "input"))
      (node (ref "R3") (pin "2") (pinfunction "2_2") (pintype "passive"))
      (node (ref "R4") (pin "2") (pinfunction "2_2") (pintype "passive"))
    )
    (net (code "38") (name "Net-(JP1-K)") (class "Default")
      (node (ref "JP1") (pin "2") (pinfunction "K_2") (pintype "passive"))
      (node (ref "Q2") (pin "D") (pinfunction "D_D") (pintype "passive"))
    )
    (net (code "39") (name "Net-(JP2-Pad1)") (class "Default")
      (node (ref "JP2") (pin "1") (pinfunction "1_1") (pintype "passive"))
      (node (ref "R21") (pin "1") (pinfunction "1_1") (pintype "passive"))
    )
    (net (code "40") (name "Net-(LED1-C)") (class "Default")
      (node (ref "LED1") (pin "K") (pinfunction "C_K") (pintype "passive"))
      (node (ref "R16") (pin "2") (pinfunction "2_2") (pintype "passive"))
    )
    (net (code "41") (name "Net-(Q2-PadG)") (class "Default")
      (node (ref "Q2") (pin "G") (pinfunction "G_G") (pintype "passive"))
      (node (ref "R13") (pin "1") (pinfunction "1_1") (pintype "passive"))
      (node (ref "T1") (pin "C") (pinfunction "C_C") (pintype "passive"))
      (node (ref "T2") (pin "C") (pinfunction "C_C") (pintype "passive"))
    )
    (net (code "42") (name "Net-(Q2-PadS)") (class "Default")
      (node (ref "Q2") (pin "S") (pinfunction "S_S") (pintype "passive"))
      (node (ref "R15") (pin "2") (pinfunction "2_2") (pintype "passive"))
      (node (ref "T2") (pin "B") (pinfunction "B_B") (pintype "passive"))
    )
    (net (code "43") (name "Net-(R11-Pad2)") (class "Default")
      (node (ref "R11") (pin "2") (pinfunction "2_2") (pintype "passive"))
      (node (ref "T1") (pin "B") (pinfunction "B_B") (pintype "passive"))
    )
    (net (code "44") (name "Net-(U1A-COM)") (class "Default")
      (node (ref "R12") (pin "1") (pinfunction "1_1") (pintype "passive"))
      (node (ref "U1") (pin "2") (pinfunction "COM_2") (pintype "bidirectional"))
    )
    (net (code "45") (name "Net-(U1A-IN)") (class "Default")
      (node (ref "R10") (pin "1") (pinfunction "1_1") (pintype "passive"))
      (node (ref "U1") (pin "7") (pinfunction "IN_7") (pintype "input"))
    )
    (net (code "46") (name "Net-(U2-GND)") (class "Default")
      (node (ref "Q3") (pin "S") (pinfunction "S_S") (pintype "passive"))
      (node (ref "U2") (pin "2") (pinfunction "GND_2") (pintype "power_in"))
    )
    (net (code "47") (name "Net-(U3-2)") (class "Default")
      (node (ref "16X2") (pin "10") (pinfunction "10_10") (pintype "passive"))
      (node (ref "U3") (pin "P$11") (pinfunction "2_P$11") (pintype "bidirectional"))
    )
    (net (code "48") (name "Net-(U3-3)") (class "Default")
      (node (ref "16X2") (pin "9") (pinfunction "9_9") (pintype "passive"))
      (node (ref "U3") (pin "P$10") (pinfunction "3_P$10") (pintype "bidirectional"))
    )
    (net (code "49") (name "Net-(U3-4)") (class "Default")
      (node (ref "16X2") (pin "8") (pinfunction "8_8") (pintype "passive"))
      (node (ref "U3") (pin "P$9") (pinfunction "4_P$9") (pintype "bidirectional"))
    )
    (net (code "50") (name "Net-(U3-5)") (class "Default")
      (node (ref "16X2") (pin "7") (pinfunction "7_7") (pintype "passive"))
      (node (ref "U3") (pin "P$8") (pinfunction "5_P$8") (pintype "bidirectional"))
    )
    (net (code "51") (name "Net-(U3-5V)") (class "Default")
      (node (ref "J1") (pin "2") (pinfunction "2_2") (pintype "passive"))
      (node (ref "U3") (pin "P$23") (pinfunction "5V_P$23") (pintype "bidirectional"))
    )
    (net (code "52") (name "Net-(U3-6)") (class "Default")
      (node (ref "16X2") (pin "6") (pinfunction "6_6") (pintype "passive"))
      (node (ref "U3") (pin "P$7") (pinfunction "6_P$7") (pintype "bidirectional"))
    )
    (net (code "53") (name "Net-(U3-7)") (class "Default")
      (node (ref "16X2") (pin "5") (pinfunction "5_5") (pintype "passive"))
      (node (ref "U3") (pin "P$6") (pinfunction "7_P$6") (pintype "bidirectional"))
    )
    (net (code "54") (name "Net-(U3-8)") (class "Default")
      (node (ref "16X2") (pin "4") (pinfunction "4_4") (pintype "passive"))
      (node (ref "U3") (pin "P$5") (pinfunction "8_P$5") (pintype "bidirectional"))
    )
    (net (code "55") (name "Net-(U3-13)") (class "Default")
      (node (ref "LED1") (pin "A") (pinfunction "A_A") (pintype "passive"))
      (node (ref "Q4") (pin "G") (pinfunction "G_G") (pintype "passive"))
      (node (ref "U3") (pin "P$34") (pinfunction "13_P$34") (pintype "bidirectional"))
    )
    (net (code "56") (name "Net-(U4--)") (class "Default")
      (node (ref "D1") (pin "A") (pinfunction "A_A") (pintype "passive"))
      (node (ref "Q4") (pin "D") (pinfunction "D_D") (pintype "passive"))
      (node (ref "U4") (pin "2") (pinfunction "-_2") (pintype "bidirectional"))
    )
    (net (code "57") (name "unconnected-(IC3B-Q-Pad9)") (class "Default")
      (node (ref "IC3") (pin "9") (pinfunction "Q_9") (pintype "output"))
    )
    (net (code "58") (name "unconnected-(IC3B-~{Q}-Pad8)") (class "Default")
      (node (ref "IC3") (pin "8") (pinfunction "~{Q}_8") (pintype "output"))
    )
    (net (code "59") (name "unconnected-(U3-3V-PadP$33)") (class "Default")
      (node (ref "U3") (pin "P$33") (pinfunction "3V_P$33") (pintype "bidirectional"))
    )
    (net (code "60") (name "unconnected-(U3-9V-PadP$20)") (class "Default")
      (node (ref "U3") (pin "P$20") (pinfunction "9V_P$20") (pintype "bidirectional"))
    )
    (net (code "61") (name "unconnected-(U3-A0-PadP$31)") (class "Default")
      (node (ref "U3") (pin "P$31") (pinfunction "A0_P$31") (pintype "bidirectional"))
    )
    (net (code "62") (name "unconnected-(U3-A1-PadP$30)") (class "Default")
      (node (ref "U3") (pin "P$30") (pinfunction "A1_P$30") (pintype "bidirectional"))
    )
    (net (code "63") (name "unconnected-(U3-A2-PadP$29)") (class "Default")
      (node (ref "U3") (pin "P$29") (pinfunction "A2_P$29") (pintype "bidirectional"))
    )
    (net (code "64") (name "unconnected-(U3-AREF-PadP$32)") (class "Default")
      (node (ref "U3") (pin "P$32") (pinfunction "AREF_P$32") (pintype "bidirectional"))
    )
    (net (code "65") (name "unconnected-(U3-GND-PadP$21)") (class "Default")
      (node (ref "U3") (pin "P$21") (pinfunction "GND_P$21") (pintype "bidirectional"))
    )
    (net (code "66") (name "unconnected-(U3-MOSI-PadP$17)") (class "Default")
      (node (ref "U3") (pin "P$17") (pinfunction "MOSI_P$17") (pintype "bidirectional"))
    )
    (net (code "67") (name "unconnected-(U3-NC-PadP$24)") (class "Default")
      (node (ref "U3") (pin "P$24") (pinfunction "NC_P$24") (pintype "bidirectional"))
    )
    (net (code "68") (name "unconnected-(U3-NC-PadP$25)") (class "Default")
      (node (ref "U3") (pin "P$25") (pinfunction "NC_P$25") (pintype "bidirectional"))
    )
    (net (code "69") (name "unconnected-(U3-R-PadP$13)") (class "Default")
      (node (ref "U3") (pin "P$13") (pinfunction "R_P$13") (pintype "bidirectional"))
    )
    (net (code "70") (name "unconnected-(U3-R-PadP$22)") (class "Default")
      (node (ref "U3") (pin "P$22") (pinfunction "R_P$22") (pintype "bidirectional"))
    )
    (net (code "71") (name "unconnected-(U3-RX-PadP$14)") (class "Default")
      (node (ref "U3") (pin "P$14") (pinfunction "RX_P$14") (pintype "bidirectional"))
    )
    (net (code "72") (name "unconnected-(U3-SS-PadP$16)") (class "Default")
      (node (ref "U3") (pin "P$16") (pinfunction "SS_P$16") (pintype "bidirectional"))
    )
    (net (code "73") (name "unconnected-(U3-TX-PadP$15)") (class "Default")
      (node (ref "U3") (pin "P$15") (pinfunction "TX_P$15") (pintype "bidirectional"))
    )
  )
)
